# rs485.net
KiCad netlist of a schematic drawn in EasyEDA
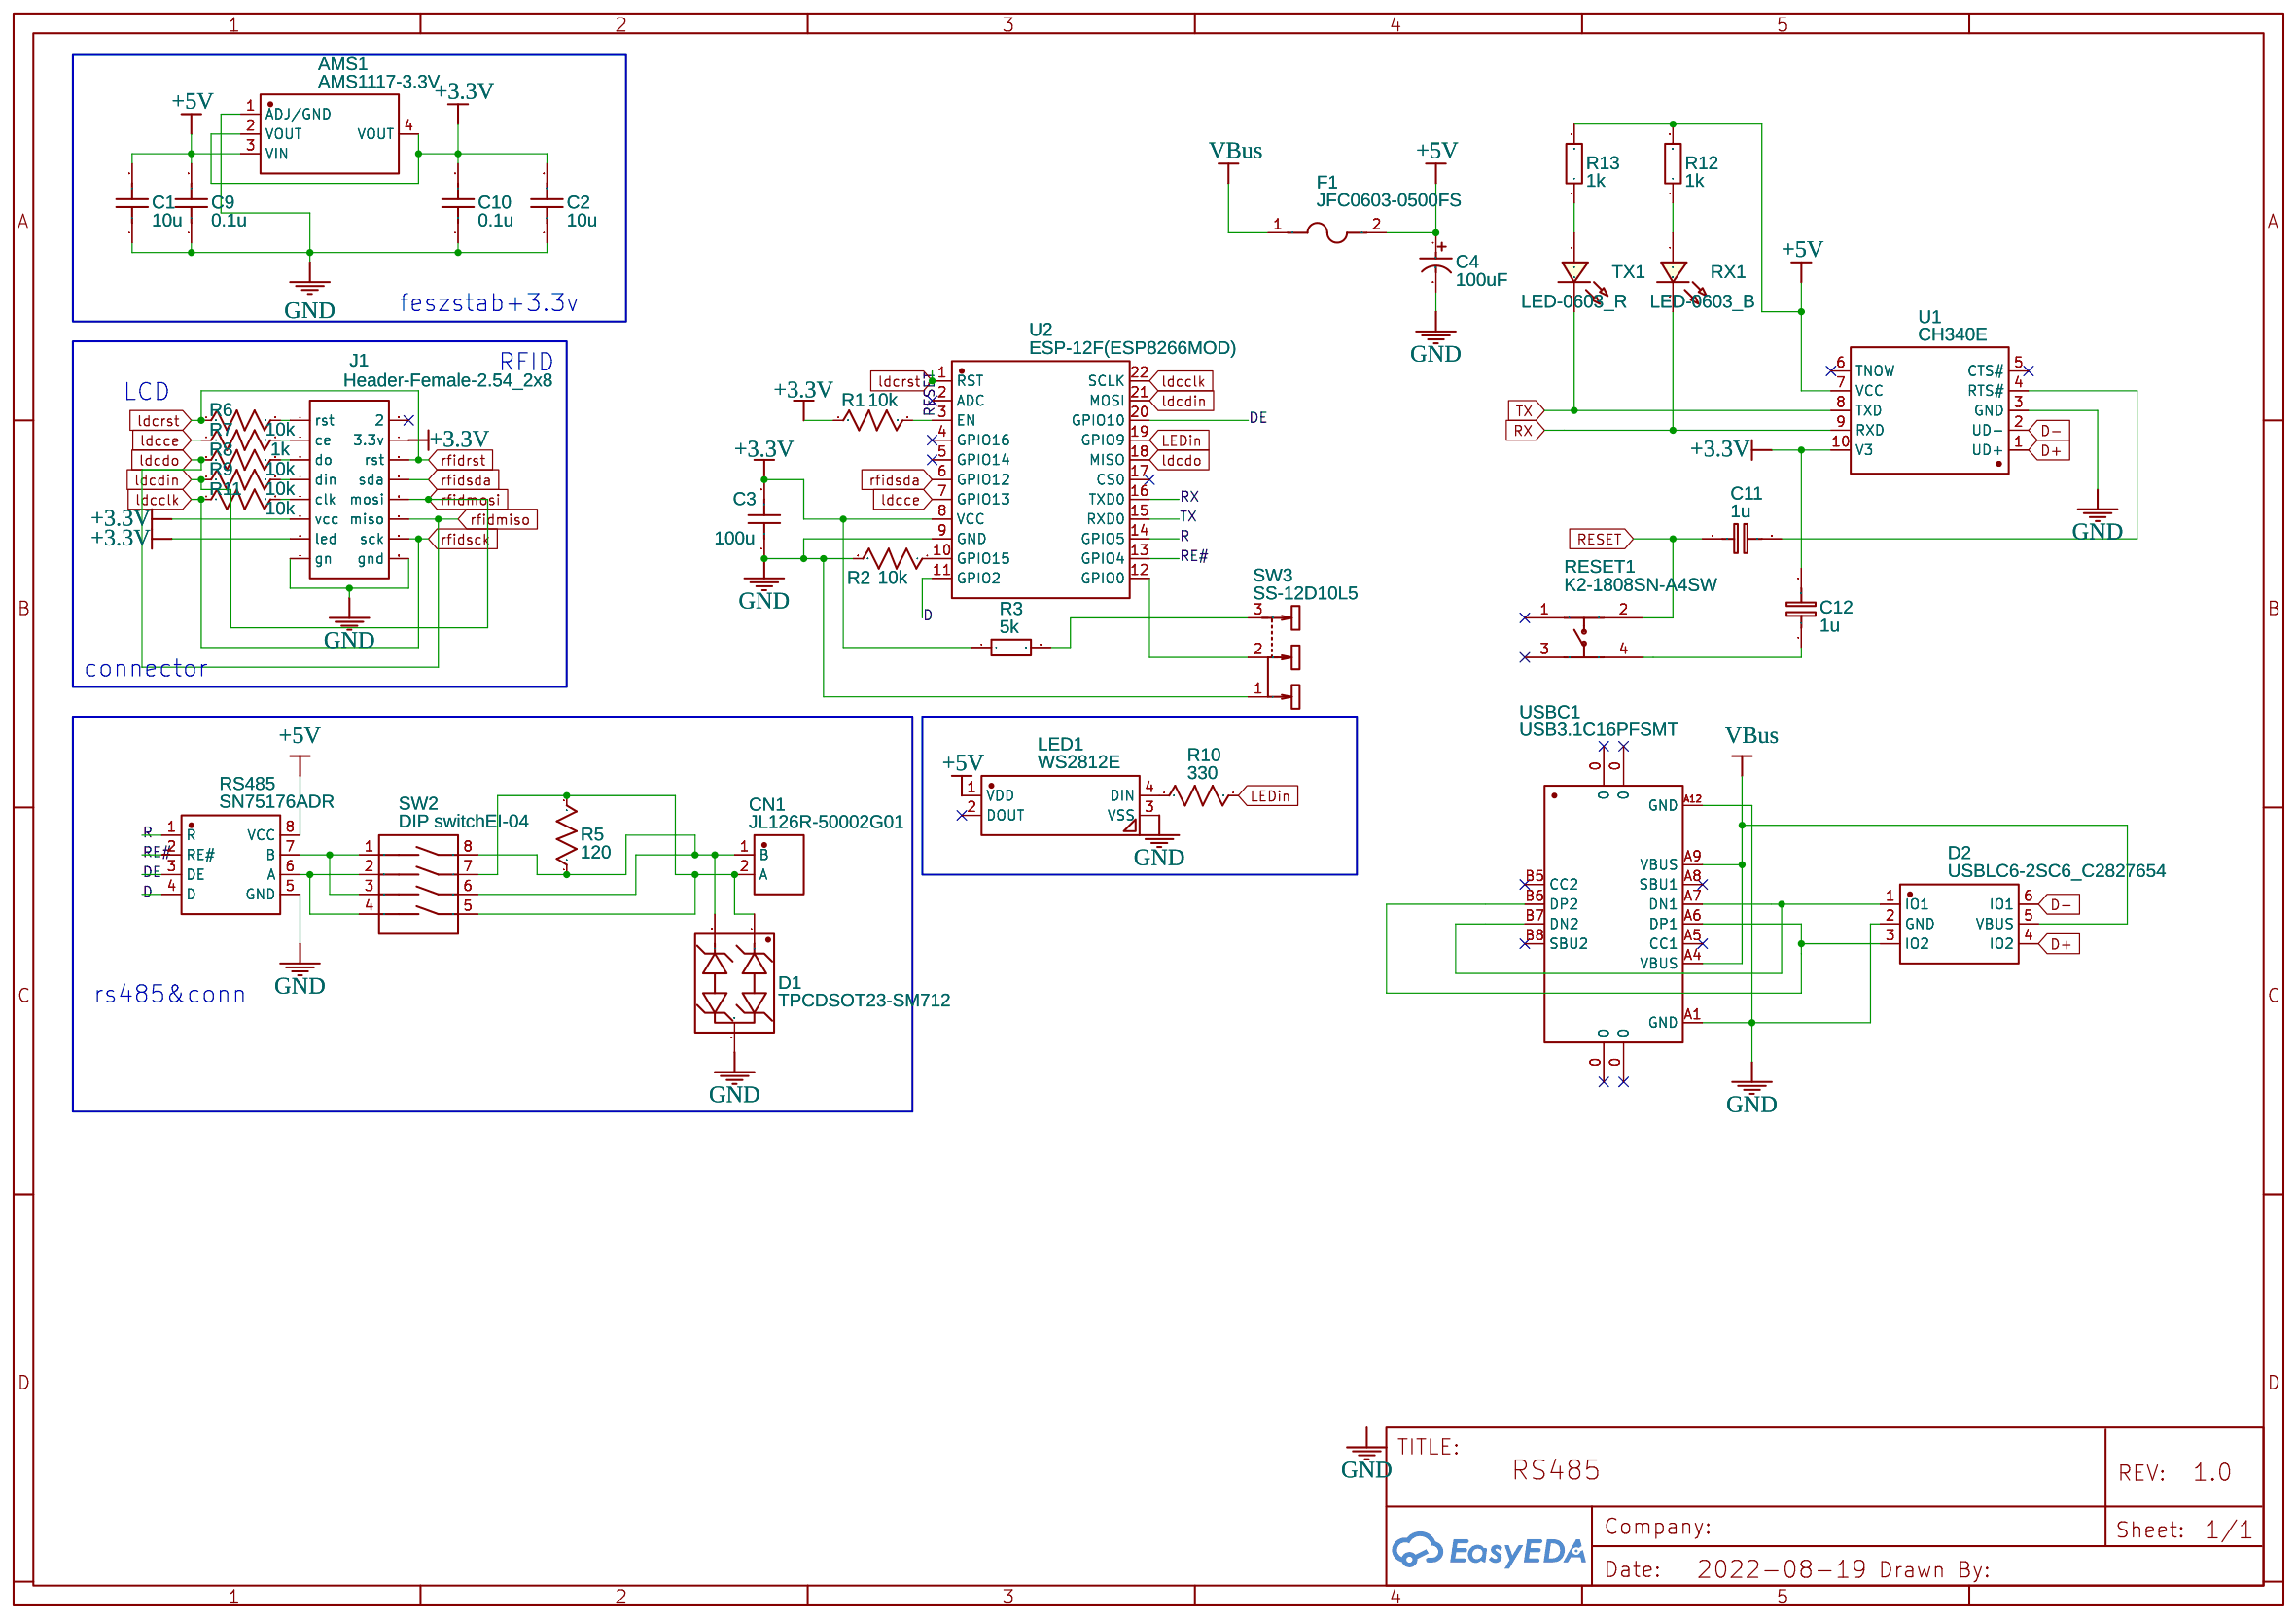
[diagram p0: schematic sheet]

(export (version "E")
  (design (tool "Eeschema 10.0.6"))
  (components
    (comp (ref "AMS1")
      (value "AMS1117-3.3V")
      (fields (field (name "BOM_Supplier Part") "C2688239"))
      (libsource (lib "") (part "AMS1117-3.3V"))
    )
    (comp (ref "C1") (value "10u") (libsource (lib "") (part "C_0603_US")))
    (comp (ref "C2") (value "10u") (libsource (lib "") (part "C_0603_US")))
    (comp (ref "C3") (value "100u") (libsource (lib "") (part "C_0603_US")))
    (comp (ref "C4")
      (value "100uF")
      (fields
        (field (name "BOM_Manufacturer Part") "RVT1A101M0505")
        (field (name "BOM_Supplier Part") "C3347")
      )
      (libsource (lib "") (part "RVT1A101M0505-C3347"))
    )
    (comp (ref "C9") (value "0.1u") (libsource (lib "") (part "C_0603_US")))
    (comp (ref "C10") (value "0.1u") (libsource (lib "") (part "C_0603_US")))
    (comp (ref "C11")
      (value "1u")
      (fields (field (name "BOM_Manufacturer Part") "?"))
      (libsource (lib "") (part "Cap_0603_EU"))
    )
    (comp (ref "C12")
      (value "1u")
      (fields (field (name "BOM_Manufacturer Part") "?"))
      (libsource (lib "") (part "Cap_0603_EU_1"))
    )
    (comp (ref "CN1")
      (value "JL126R-50002G01")
      (fields (field (name "BOM_Supplier Part") "C415452"))
      (libsource (lib "") (part "JL126R-50002G01"))
    )
    (comp (ref "D1")
      (value "TPCDSOT23-SM712")
      (fields (field (name "BOM_Supplier Part") "C558433"))
      (libsource (lib "") (part "TPCDSOT23-SM712"))
    )
    (comp (ref "D2")
      (value "USBLC6-2SC6_C2827654")
      (fields
        (field (name "BOM_Manufacturer Part") "USBLC6-2SC6")
        (field (name "BOM_Supplier Part") "C2827654")
      )
      (libsource (lib "") (part "USBLC6-2SC6_C2827654"))
    )
    (comp (ref "F1")
      (value "JFC0603-0500FS")
      (fields (field (name "BOM_Supplier Part") "C136327"))
      (libsource (lib "") (part "JFC0603-0500FS"))
    )
    (comp (ref "J1")
      (value "Header-Female-2.54_2x8")
      (fields
        (field (name "BOM_Manufacturer Part") "2.54mm,2×8Double female header")
        (field (name "BOM_Supplier Part") "C30734")
      )
      (libsource (lib "") (part "Header-Female-2.54_2x8"))
    )
    (comp (ref "LED1")
      (value "WS2812E")
      (fields (field (name "BOM_Supplier Part") "C139127"))
      (libsource (lib "") (part "WS2812E"))
    )
    (comp (ref "R1") (value "10k") (libsource (lib "") (part "R_0603_US")))
    (comp (ref "R2") (value "10k") (libsource (lib "") (part "R_0603_US_2")))
    (comp (ref "R3")
      (value "5k")
      (fields
        (field (name "BOM_Manufacturer Part") "RS-03K102JT")
        (field (name "BOM_Supplier Part") "C73797")
      )
      (libsource (lib "") (part "RS-03K102JT_1"))
    )
    (comp (ref "R5") (value "120") (libsource (lib "") (part "R_0603_US_1")))
    (comp (ref "R6") (value "10k") (libsource (lib "") (part "R_0603_US")))
    (comp (ref "R7") (value "1k") (libsource (lib "") (part "R_0603_US")))
    (comp (ref "R8") (value "10k") (libsource (lib "") (part "R_0603_US")))
    (comp (ref "R9") (value "10k") (libsource (lib "") (part "R_0603_US")))
    (comp (ref "R10") (value "330") (libsource (lib "") (part "R_0603_US")))
    (comp (ref "R11") (value "10k") (libsource (lib "") (part "R_0603_US")))
    (comp (ref "R12")
      (value "1k")
      (fields
        (field (name "BOM_Manufacturer Part") "RS-03K102JT")
        (field (name "BOM_Supplier Part") "C73797")
      )
      (libsource (lib "") (part "RS-03K102JT"))
    )
    (comp (ref "R13")
      (value "1k")
      (fields
        (field (name "BOM_Manufacturer Part") "RS-03K102JT")
        (field (name "BOM_Supplier Part") "C73797")
      )
      (libsource (lib "") (part "RS-03K102JT"))
    )
    (comp (ref "RESET1")
      (value "K2-1808SN-A4SW")
      (fields (field (name "BOM_Supplier Part") "C92589"))
      (libsource (lib "") (part "K2-1808SN-A4SW"))
    )
    (comp (ref "RS485")
      (value "SN75176ADR")
      (fields (field (name "BOM_Supplier Part") "C468242"))
      (libsource (lib "") (part "SN75176ADR"))
    )
    (comp (ref "RX1")
      (value "LED-0603_B")
      (fields
        (field (name "BOM_Manufacturer Part") "19-217/BHC-ZL1M2RY/3T")
        (field (name "BOM_Supplier Part") "C72041")
      )
      (libsource (lib "") (part "LED-0603_B"))
    )
    (comp (ref "SW2")
      (value "DIP switchEI-04")
      (fields (field (name "BOM_Supplier Part") "C99987"))
      (libsource (lib "") (part "DIP switchEI-04"))
    )
    (comp (ref "SW3")
      (value "SS-12D10L5")
      (fields (field (name "BOM_Supplier Part") "C319012"))
      (libsource (lib "") (part "SS-12D10L5"))
    )
    (comp (ref "TX1")
      (value "LED-0603_R")
      (fields
        (field (name "BOM_Manufacturer Part") "19-217/R6C-AL1M2VY/3T")
        (field (name "BOM_Supplier Part") "C72044")
      )
      (libsource (lib "") (part "LED-0603_R"))
    )
    (comp (ref "U1")
      (value "CH340E")
      (fields (field (name "BOM_Supplier Part") "C99652"))
      (libsource (lib "") (part "CH340E"))
    )
    (comp (ref "U2")
      (value "ESP-12F(ESP8266MOD)")
      (fields (field (name "BOM_Supplier Part") "C82891"))
      (libsource (lib "") (part "ESP-12F(ESP8266MOD)"))
    )
    (comp (ref "USBC1")
      (value "USB3.1C16PFSMT")
      (fields (field (name "BOM_Supplier Part") "C167321"))
      (libsource (lib "") (part "USB3.1C16PFSMT"))
    )
  )
  (nets
    (net (code "1") (name "+3.3V") (class "Default")
      (node (ref "AMS1") (pin "2") (pinfunction "VOUT_2") (pintype "unspecified"))
      (node (ref "AMS1") (pin "4") (pinfunction "VOUT_4") (pintype "unspecified"))
      (node (ref "C10") (pin "2") (pinfunction "2_2") (pintype "unspecified"))
      (node (ref "C12") (pin "2") (pinfunction "2_2") (pintype "unspecified"))
      (node (ref "C2") (pin "2") (pinfunction "2_2") (pintype "unspecified"))
      (node (ref "C3") (pin "2") (pinfunction "2_2") (pintype "unspecified"))
      (node (ref "J1") (pin "11") (pinfunction "vcc_11") (pintype "input"))
      (node (ref "J1") (pin "13") (pinfunction "led_13") (pintype "input"))
      (node (ref "J1") (pin "4") (pinfunction "3.3v_4") (pintype "input"))
      (node (ref "R1") (pin "1") (pinfunction "1_1") (pintype "unspecified"))
      (node (ref "R3") (pin "1") (pinfunction "1_1") (pintype "input"))
      (node (ref "U1") (pin "10") (pinfunction "V3_10") (pintype "unspecified"))
      (node (ref "U2") (pin "8") (pinfunction "VCC_8") (pintype "unspecified"))
    )
    (net (code "2") (name "+5V") (class "Default")
      (node (ref "AMS1") (pin "3") (pinfunction "VIN_3") (pintype "unspecified"))
      (node (ref "C1") (pin "2") (pinfunction "2_2") (pintype "unspecified"))
      (node (ref "C4") (pin "1") (pinfunction "1_1") (pintype "input"))
      (node (ref "C9") (pin "2") (pinfunction "2_2") (pintype "unspecified"))
      (node (ref "F1") (pin "2") (pinfunction "2_2") (pintype "unspecified"))
      (node (ref "LED1") (pin "1") (pinfunction "VDD_1") (pintype "unspecified"))
      (node (ref "R12") (pin "2") (pinfunction "2_2") (pintype "input"))
      (node (ref "R13") (pin "2") (pinfunction "2_2") (pintype "input"))
      (node (ref "RS485") (pin "8") (pinfunction "VCC_8") (pintype "unspecified"))
      (node (ref "U1") (pin "7") (pinfunction "VCC_7") (pintype "unspecified"))
    )
    (net (code "3") (name "/D") (class "Default")
      (node (ref "RS485") (pin "4") (pinfunction "D_4") (pintype "unspecified"))
      (node (ref "U2") (pin "11") (pinfunction "GPIO2_11") (pintype "unspecified"))
    )
    (net (code "4") (name "/DE") (class "Default")
      (node (ref "RS485") (pin "3") (pinfunction "DE_3") (pintype "unspecified"))
      (node (ref "U2") (pin "20") (pinfunction "GPIO10_20") (pintype "unspecified"))
    )
    (net (code "5") (name "/R") (class "Default")
      (node (ref "RS485") (pin "1") (pinfunction "R_1") (pintype "unspecified"))
      (node (ref "U2") (pin "14") (pinfunction "GPIO5_14") (pintype "unspecified"))
    )
    (net (code "6") (name "/RE#") (class "Default")
      (node (ref "RS485") (pin "2") (pinfunction "RE#_2") (pintype "unspecified"))
      (node (ref "U2") (pin "13") (pinfunction "GPIO4_13") (pintype "unspecified"))
    )
    (net (code "7") (name "D+") (class "Default")
      (node (ref "D2") (pin "4") (pinfunction "IO2_4") (pintype "unspecified"))
      (node (ref "U1") (pin "1") (pinfunction "UD+_1") (pintype "unspecified"))
    )
    (net (code "8") (name "D-") (class "Default")
      (node (ref "D2") (pin "6") (pinfunction "IO1_6") (pintype "unspecified"))
      (node (ref "U1") (pin "2") (pinfunction "UD-_2") (pintype "unspecified"))
    )
    (net (code "9") (name "GND") (class "Default")
      (node (ref "AMS1") (pin "1") (pinfunction "ADJ/GND_1") (pintype "unspecified"))
      (node (ref "C1") (pin "1") (pinfunction "1_1") (pintype "unspecified"))
      (node (ref "C10") (pin "1") (pinfunction "1_1") (pintype "unspecified"))
      (node (ref "C2") (pin "1") (pinfunction "1_1") (pintype "unspecified"))
      (node (ref "C3") (pin "1") (pinfunction "1_1") (pintype "unspecified"))
      (node (ref "C4") (pin "2") (pinfunction "2_2") (pintype "input"))
      (node (ref "C9") (pin "1") (pinfunction "1_1") (pintype "unspecified"))
      (node (ref "D1") (pin "3") (pinfunction "3_3") (pintype "unspecified"))
      (node (ref "D2") (pin "2") (pinfunction "GND_2") (pintype "unspecified"))
      (node (ref "J1") (pin "15") (pinfunction "gn_15") (pintype "input"))
      (node (ref "J1") (pin "16") (pinfunction "gnd_16") (pintype "input"))
      (node (ref "LED1") (pin "3") (pinfunction "VSS_3") (pintype "unspecified"))
      (node (ref "R2") (pin "2") (pinfunction "2_2") (pintype "unspecified"))
      (node (ref "RS485") (pin "5") (pinfunction "GND_5") (pintype "unspecified"))
      (node (ref "SW3") (pin "1") (pinfunction "1_1") (pintype "unspecified"))
      (node (ref "U1") (pin "3") (pinfunction "GND_3") (pintype "unspecified"))
      (node (ref "U2") (pin "9") (pinfunction "GND_9") (pintype "unspecified"))
      (node (ref "USBC1") (pin "A1") (pinfunction "GND_A1") (pintype "unspecified"))
      (node (ref "USBC1") (pin "A12") (pinfunction "GND_A12") (pintype "unspecified"))
    )
    (net (code "10") (name "LEDin") (class "Default")
      (node (ref "R10") (pin "2") (pinfunction "2_2") (pintype "unspecified"))
      (node (ref "U2") (pin "19") (pinfunction "GPIO9_19") (pintype "unspecified"))
    )
    (net (code "11") (name "Net-(C12-Pad1)") (class "Default")
      (node (ref "C12") (pin "1") (pinfunction "1_1") (pintype "unspecified"))
      (node (ref "RESET1") (pin "4") (pinfunction "4_4") (pintype "unspecified"))
    )
    (net (code "12") (name "Net-(CN1-A)") (class "Default")
      (node (ref "CN1") (pin "2") (pinfunction "A_2") (pintype "unspecified"))
      (node (ref "D1") (pin "1") (pinfunction "1_1") (pintype "unspecified"))
      (node (ref "R5") (pin "2") (pinfunction "2_2") (pintype "unspecified"))
      (node (ref "SW2") (pin "5") (pinfunction "5_5") (pintype "unspecified"))
      (node (ref "SW2") (pin "7") (pinfunction "7_7") (pintype "unspecified"))
    )
    (net (code "13") (name "Net-(CN1-B)") (class "Default")
      (node (ref "CN1") (pin "1") (pinfunction "B_1") (pintype "unspecified"))
      (node (ref "D1") (pin "2") (pinfunction "2_2") (pintype "unspecified"))
      (node (ref "R5") (pin "1") (pinfunction "1_1") (pintype "unspecified"))
      (node (ref "SW2") (pin "6") (pinfunction "6_6") (pintype "unspecified"))
      (node (ref "SW2") (pin "8") (pinfunction "8_8") (pintype "unspecified"))
    )
    (net (code "14") (name "Net-(J1-ce)") (class "Default")
      (node (ref "J1") (pin "3") (pinfunction "ce_3") (pintype "input"))
      (node (ref "R7") (pin "2") (pinfunction "2_2") (pintype "unspecified"))
    )
    (net (code "15") (name "Net-(J1-clk)") (class "Default")
      (node (ref "J1") (pin "9") (pinfunction "clk_9") (pintype "input"))
      (node (ref "R11") (pin "2") (pinfunction "2_2") (pintype "unspecified"))
    )
    (net (code "16") (name "Net-(J1-din)") (class "Default")
      (node (ref "J1") (pin "7") (pinfunction "din_7") (pintype "input"))
      (node (ref "R9") (pin "2") (pinfunction "2_2") (pintype "unspecified"))
    )
    (net (code "17") (name "Net-(J1-do)") (class "Default")
      (node (ref "J1") (pin "5") (pinfunction "do_5") (pintype "input"))
      (node (ref "R8") (pin "2") (pinfunction "2_2") (pintype "unspecified"))
    )
    (net (code "18") (name "Net-(J1-rst-Pad1)") (class "Default")
      (node (ref "J1") (pin "1") (pinfunction "rst_1") (pintype "input"))
      (node (ref "R6") (pin "2") (pinfunction "2_2") (pintype "unspecified"))
    )
    (net (code "19") (name "Net-(LED1-DIN)") (class "Default")
      (node (ref "LED1") (pin "4") (pinfunction "DIN_4") (pintype "unspecified"))
      (node (ref "R10") (pin "1") (pinfunction "1_1") (pintype "unspecified"))
    )
    (net (code "20") (name "Net-(R3-Pad2)") (class "Default")
      (node (ref "R3") (pin "2") (pinfunction "2_2") (pintype "input"))
      (node (ref "SW3") (pin "3") (pinfunction "3_3") (pintype "unspecified"))
    )
    (net (code "21") (name "Net-(R12-Pad1)") (class "Default")
      (node (ref "R12") (pin "1") (pinfunction "1_1") (pintype "input"))
      (node (ref "RX1") (pin "1") (pinfunction "1_1") (pintype "unspecified"))
    )
    (net (code "22") (name "Net-(R13-Pad1)") (class "Default")
      (node (ref "R13") (pin "1") (pinfunction "1_1") (pintype "input"))
      (node (ref "TX1") (pin "1") (pinfunction "1_1") (pintype "unspecified"))
    )
    (net (code "23") (name "Net-(RS485-A)") (class "Default")
      (node (ref "RS485") (pin "6") (pinfunction "A_6") (pintype "unspecified"))
      (node (ref "SW2") (pin "2") (pinfunction "2_2") (pintype "unspecified"))
      (node (ref "SW2") (pin "4") (pinfunction "4_4") (pintype "unspecified"))
    )
    (net (code "24") (name "Net-(RS485-B)") (class "Default")
      (node (ref "RS485") (pin "7") (pinfunction "B_7") (pintype "unspecified"))
      (node (ref "SW2") (pin "1") (pinfunction "1_1") (pintype "unspecified"))
      (node (ref "SW2") (pin "3") (pinfunction "3_3") (pintype "unspecified"))
    )
    (net (code "25") (name "Net-(U1-RTS#)") (class "Default")
      (node (ref "C11") (pin "2") (pinfunction "2_2") (pintype "unspecified"))
      (node (ref "U1") (pin "4") (pinfunction "RTS#_4") (pintype "unspecified"))
    )
    (net (code "26") (name "Net-(U2-EN)") (class "Default")
      (node (ref "R1") (pin "2") (pinfunction "2_2") (pintype "unspecified"))
      (node (ref "U2") (pin "3") (pinfunction "EN_3") (pintype "unspecified"))
    )
    (net (code "27") (name "Net-(U2-GPIO0)") (class "Default")
      (node (ref "SW3") (pin "2") (pinfunction "2_2") (pintype "unspecified"))
      (node (ref "U2") (pin "12") (pinfunction "GPIO0_12") (pintype "unspecified"))
    )
    (net (code "28") (name "Net-(U2-GPIO15)") (class "Default")
      (node (ref "R2") (pin "1") (pinfunction "1_1") (pintype "unspecified"))
      (node (ref "U2") (pin "10") (pinfunction "GPIO15_10") (pintype "unspecified"))
    )
    (net (code "29") (name "Net-(USBC1-DN1)") (class "Default")
      (node (ref "D2") (pin "1") (pinfunction "IO1_1") (pintype "unspecified"))
      (node (ref "USBC1") (pin "A7") (pinfunction "DN1_A7") (pintype "unspecified"))
      (node (ref "USBC1") (pin "B7") (pinfunction "DN2_B7") (pintype "unspecified"))
    )
    (net (code "30") (name "Net-(USBC1-DP1)") (class "Default")
      (node (ref "D2") (pin "3") (pinfunction "IO2_3") (pintype "unspecified"))
      (node (ref "USBC1") (pin "A6") (pinfunction "DP1_A6") (pintype "unspecified"))
      (node (ref "USBC1") (pin "B6") (pinfunction "DP2_B6") (pintype "unspecified"))
    )
    (net (code "31") (name "RESET") (class "Default")
      (node (ref "C11") (pin "1") (pinfunction "1_1") (pintype "unspecified"))
      (node (ref "J1") (pin "6") (pinfunction "rst_6") (pintype "input"))
      (node (ref "R6") (pin "1") (pinfunction "1_1") (pintype "unspecified"))
      (node (ref "RESET1") (pin "2") (pinfunction "2_2") (pintype "unspecified"))
      (node (ref "U2") (pin "1") (pinfunction "RST_1") (pintype "unspecified"))
    )
    (net (code "32") (name "RX") (class "Default")
      (node (ref "RX1") (pin "2") (pinfunction "2_2") (pintype "unspecified"))
      (node (ref "U1") (pin "9") (pinfunction "RXD_9") (pintype "unspecified"))
      (node (ref "U2") (pin "16") (pinfunction "TXD0_16") (pintype "unspecified"))
    )
    (net (code "33") (name "TX") (class "Default")
      (node (ref "TX1") (pin "2") (pinfunction "2_2") (pintype "unspecified"))
      (node (ref "U1") (pin "8") (pinfunction "TXD_8") (pintype "unspecified"))
      (node (ref "U2") (pin "15") (pinfunction "RXD0_15") (pintype "unspecified"))
    )
    (net (code "34") (name "VBus") (class "Default")
      (node (ref "D2") (pin "5") (pinfunction "VBUS_5") (pintype "unspecified"))
      (node (ref "F1") (pin "1") (pinfunction "1_1") (pintype "unspecified"))
      (node (ref "USBC1") (pin "A4") (pinfunction "VBUS_A4") (pintype "unspecified"))
      (node (ref "USBC1") (pin "A9") (pinfunction "VBUS_A9") (pintype "unspecified"))
    )
    (net (code "35") (name "ldcce") (class "Default")
      (node (ref "R7") (pin "1") (pinfunction "1_1") (pintype "unspecified"))
      (node (ref "U2") (pin "7") (pinfunction "GPIO13_7") (pintype "unspecified"))
    )
    (net (code "36") (name "ldcclk") (class "Default")
      (node (ref "J1") (pin "14") (pinfunction "sck_14") (pintype "input"))
      (node (ref "R11") (pin "1") (pinfunction "1_1") (pintype "unspecified"))
      (node (ref "U2") (pin "22") (pinfunction "SCLK_22") (pintype "unspecified"))
    )
    (net (code "37") (name "ldcdin") (class "Default")
      (node (ref "J1") (pin "10") (pinfunction "mosi_10") (pintype "input"))
      (node (ref "R9") (pin "1") (pinfunction "1_1") (pintype "unspecified"))
      (node (ref "U2") (pin "21") (pinfunction "MOSI_21") (pintype "unspecified"))
    )
    (net (code "38") (name "ldcdo") (class "Default")
      (node (ref "J1") (pin "12") (pinfunction "miso_12") (pintype "input"))
      (node (ref "R8") (pin "1") (pinfunction "1_1") (pintype "unspecified"))
      (node (ref "U2") (pin "18") (pinfunction "MISO_18") (pintype "unspecified"))
    )
    (net (code "39") (name "rfidsda") (class "Default")
      (node (ref "J1") (pin "8") (pinfunction "sda_8") (pintype "input"))
      (node (ref "U2") (pin "6") (pinfunction "GPIO12_6") (pintype "unspecified"))
    )
    (net (code "40") (name "unconnected-(J1-Pad2)") (class "Default")
      (node (ref "J1") (pin "2") (pinfunction "2_2") (pintype "input+no_connect"))
    )
    (net (code "41") (name "unconnected-(LED1-DOUT-Pad2)") (class "Default")
      (node (ref "LED1") (pin "2") (pinfunction "DOUT_2") (pintype "unspecified+no_connect"))
    )
    (net (code "42") (name "unconnected-(RESET1-Pad1)") (class "Default")
      (node (ref "RESET1") (pin "1") (pinfunction "1_1") (pintype "unspecified+no_connect"))
    )
    (net (code "43") (name "unconnected-(RESET1-Pad3)") (class "Default")
      (node (ref "RESET1") (pin "3") (pinfunction "3_3") (pintype "unspecified+no_connect"))
    )
    (net (code "44") (name "unconnected-(U1-CTS#-Pad5)") (class "Default")
      (node (ref "U1") (pin "5") (pinfunction "CTS#_5") (pintype "unspecified+no_connect"))
    )
    (net (code "45") (name "unconnected-(U1-TNOW-Pad6)") (class "Default")
      (node (ref "U1") (pin "6") (pinfunction "TNOW_6") (pintype "unspecified+no_connect"))
    )
    (net (code "46") (name "unconnected-(U2-ADC-Pad2)") (class "Default")
      (node (ref "U2") (pin "2") (pinfunction "ADC_2") (pintype "unspecified+no_connect"))
    )
    (net (code "47") (name "unconnected-(U2-CS0-Pad17)") (class "Default")
      (node (ref "U2") (pin "17") (pinfunction "CS0_17") (pintype "unspecified+no_connect"))
    )
    (net (code "48") (name "unconnected-(U2-GPIO14-Pad5)") (class "Default")
      (node (ref "U2") (pin "5") (pinfunction "GPIO14_5") (pintype "unspecified+no_connect"))
    )
    (net (code "49") (name "unconnected-(U2-GPIO16-Pad4)") (class "Default")
      (node (ref "U2") (pin "4") (pinfunction "GPIO16_4") (pintype "unspecified+no_connect"))
    )
    (net (code "50") (name "unconnected-(USBC1-CC1-PadA5)") (class "Default")
      (node (ref "USBC1") (pin "A5") (pinfunction "CC1_A5") (pintype "unspecified+no_connect"))
    )
    (net (code "51") (name "unconnected-(USBC1-CC2-PadB5)") (class "Default")
      (node (ref "USBC1") (pin "B5") (pinfunction "CC2_B5") (pintype "unspecified+no_connect"))
    )
    (net (code "52") (name "unconnected-(USBC1-Pad0)") (class "Default")
      (node (ref "USBC1") (pin "0") (pinfunction "0_0") (pintype "unspecified+no_connect"))
    )
    (net (code "53") (name "unconnected-(USBC1-Pad0)_1") (class "Default")
      (node (ref "USBC1") (pin "0") (pinfunction "0_0") (pintype "unspecified+no_connect"))
    )
    (net (code "54") (name "unconnected-(USBC1-Pad0)_2") (class "Default")
      (node (ref "USBC1") (pin "0") (pinfunction "0_0") (pintype "unspecified+no_connect"))
    )
    (net (code "55") (name "unconnected-(USBC1-Pad0)_3") (class "Default")
      (node (ref "USBC1") (pin "0") (pinfunction "0_0") (pintype "unspecified+no_connect"))
    )
    (net (code "56") (name "unconnected-(USBC1-SBU1-PadA8)") (class "Default")
      (node (ref "USBC1") (pin "A8") (pinfunction "SBU1_A8") (pintype "unspecified+no_connect"))
    )
    (net (code "57") (name "unconnected-(USBC1-SBU2-PadB8)") (class "Default")
      (node (ref "USBC1") (pin "B8") (pinfunction "SBU2_B8") (pintype "unspecified+no_connect"))
    )
  )
)
